# MCU.net
KiCad netlist of a schematic drawn in Altium Designer
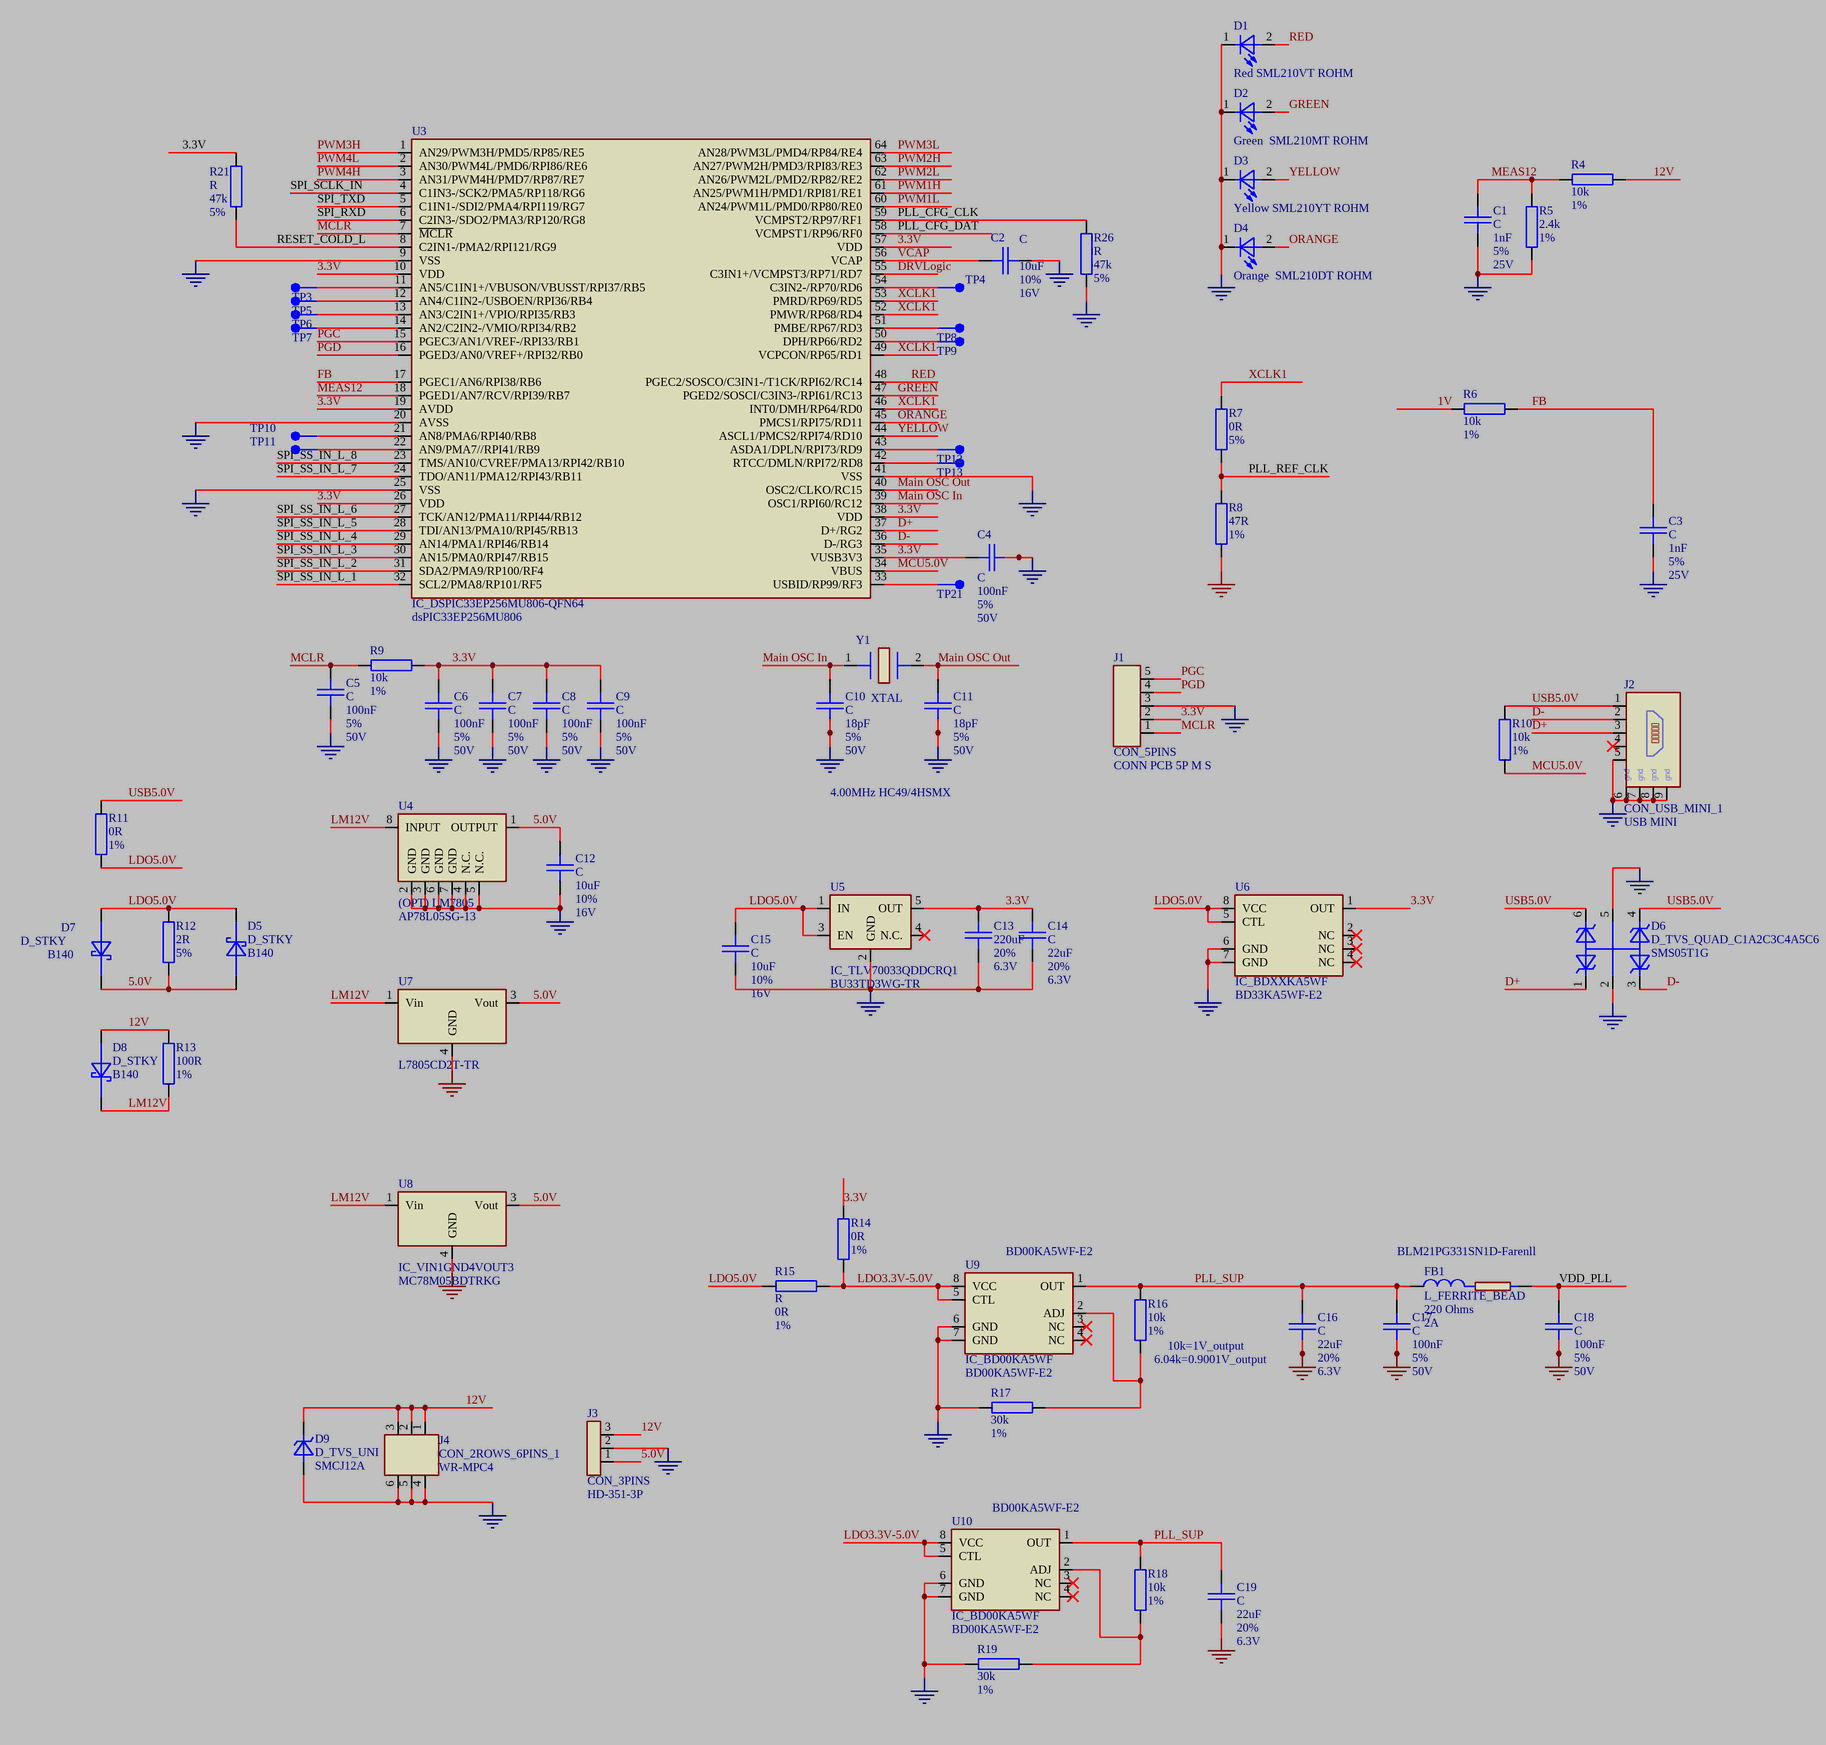
[diagram p0: MCU.SchDoc]

(export (version "E")
  (design (tool "Eeschema 10.0.6"))
  (components
    (comp (ref "C1")
      (value "C")
      (footprint "SMD_0603_CAPC1608X95N")
      (fields
        (field (name "DB_PART_NUMBER") "CAP000024113")
        (field (name "DB_VALUE") "1nF")
        (field (name "DB_TOLERANCE") "5%")
        (field (name "DB_VOLTAGE") "25V")
        (field (name "DB_MANUFACTURER_PART") "KEMET    C0603C102J3RAC")
        (field (name "DB_APPROVED_BY") "ISHIDDEN=T")
      )
      (libsource (lib "Database_Libs1") (part "C"))
    )
    (comp (ref "C2")
      (value "C")
      (footprint "SMD_0805_CAPC2012X145N")
      (fields
        (field (name "DB_PART_NUMBER") "CAP000043636")
        (field (name "DB_VALUE") "10uF")
        (field (name "DB_TOLERANCE") "10%")
        (field (name "DB_VOLTAGE") "16V")
        (field (name "DB_MANUFACTURER_PART") "KEMET    C0805C106K4PAC")
        (field (name "DB_APPROVED_BY") "ISHIDDEN=T")
      )
      (libsource (lib "Database_Libs1") (part "C"))
    )
    (comp (ref "C3")
      (value "C")
      (footprint "SMD_0603_CAPC1608X95N")
      (fields
        (field (name "DB_PART_NUMBER") "CAP000024113")
        (field (name "DB_VALUE") "1nF")
        (field (name "DB_TOLERANCE") "5%")
        (field (name "DB_VOLTAGE") "25V")
        (field (name "DB_MANUFACTURER_PART") "KEMET    C0603C102J3RAC")
        (field (name "DB_APPROVED_BY") "ISHIDDEN=T")
      )
      (libsource (lib "Database_Libs1") (part "C"))
    )
    (comp (ref "C4")
      (value "C")
      (footprint "SMD_0603_CAPC1608X95N")
      (fields
        (field (name "DB_PART_NUMBER") "CAP000027136")
        (field (name "DB_VALUE") "100nF")
        (field (name "DB_TOLERANCE") "5%")
        (field (name "DB_VOLTAGE") "50V")
        (field (name "DB_MANUFACTURER_PART") "KEMET    C0603C104J5RAC")
        (field (name "DB_APPROVED_BY") "ISHIDDEN=T")
      )
      (libsource (lib "Database_Libs1") (part "C"))
    )
    (comp (ref "C5")
      (value "C")
      (footprint "SMD_0603_CAPC1608X95N")
      (fields
        (field (name "DB_PART_NUMBER") "CAP000027136")
        (field (name "DB_VALUE") "100nF")
        (field (name "DB_TOLERANCE") "5%")
        (field (name "DB_VOLTAGE") "50V")
        (field (name "DB_MANUFACTURER_PART") "KEMET    C0603C104J5RAC")
        (field (name "DB_APPROVED_BY") "ISHIDDEN=T")
      )
      (libsource (lib "Database_Libs1") (part "C"))
    )
    (comp (ref "C6")
      (value "C")
      (footprint "SMD_0603_CAPC1608X95N")
      (fields
        (field (name "DB_PART_NUMBER") "CAP000027136")
        (field (name "DB_VALUE") "100nF")
        (field (name "DB_TOLERANCE") "5%")
        (field (name "DB_VOLTAGE") "50V")
        (field (name "DB_MANUFACTURER_PART") "KEMET    C0603C104J5RAC")
        (field (name "DB_APPROVED_BY") "ISHIDDEN=T")
      )
      (libsource (lib "Database_Libs1") (part "C"))
    )
    (comp (ref "C7")
      (value "C")
      (footprint "SMD_0603_CAPC1608X95N")
      (fields
        (field (name "DB_PART_NUMBER") "CAP000027136")
        (field (name "DB_VALUE") "100nF")
        (field (name "DB_TOLERANCE") "5%")
        (field (name "DB_VOLTAGE") "50V")
        (field (name "DB_MANUFACTURER_PART") "KEMET    C0603C104J5RAC")
        (field (name "DB_APPROVED_BY") "ISHIDDEN=T")
      )
      (libsource (lib "Database_Libs1") (part "C"))
    )
    (comp (ref "C8")
      (value "C")
      (footprint "SMD_0603_CAPC1608X95N")
      (fields
        (field (name "DB_PART_NUMBER") "CAP000027136")
        (field (name "DB_VALUE") "100nF")
        (field (name "DB_TOLERANCE") "5%")
        (field (name "DB_VOLTAGE") "50V")
        (field (name "DB_MANUFACTURER_PART") "KEMET    C0603C104J5RAC")
        (field (name "DB_APPROVED_BY") "ISHIDDEN=T")
      )
      (libsource (lib "Database_Libs1") (part "C"))
    )
    (comp (ref "C9")
      (value "C")
      (footprint "SMD_0603_CAPC1608X95N")
      (fields
        (field (name "DB_PART_NUMBER") "CAP000027136")
        (field (name "DB_VALUE") "100nF")
        (field (name "DB_TOLERANCE") "5%")
        (field (name "DB_VOLTAGE") "50V")
        (field (name "DB_MANUFACTURER_PART") "KEMET    C0603C104J5RAC")
        (field (name "DB_APPROVED_BY") "ISHIDDEN=T")
      )
      (libsource (lib "Database_Libs1") (part "C"))
    )
    (comp (ref "C10")
      (value "C")
      (footprint "SMD_0603_CAPC1608X95N")
      (fields
        (field (name "DB_PART_NUMBER") "CAP000031922")
        (field (name "DB_VALUE") "18pF")
        (field (name "DB_TOLERANCE") "5%")
        (field (name "DB_VOLTAGE") "50V")
        (field (name "DB_MANUFACTURER_PART") "KEMET    C0603C180J5GAC")
        (field (name "DB_APPROVED_BY") "ISHIDDEN=T")
      )
      (libsource (lib "Database_Libs1") (part "C"))
    )
    (comp (ref "C11")
      (value "C")
      (footprint "SMD_0603_CAPC1608X95N")
      (fields
        (field (name "DB_PART_NUMBER") "CAP000031922")
        (field (name "DB_VALUE") "18pF")
        (field (name "DB_TOLERANCE") "5%")
        (field (name "DB_VOLTAGE") "50V")
        (field (name "DB_MANUFACTURER_PART") "KEMET    C0603C180J5GAC")
        (field (name "DB_APPROVED_BY") "ISHIDDEN=T")
      )
      (libsource (lib "Database_Libs1") (part "C"))
    )
    (comp (ref "C12")
      (value "C")
      (footprint "SMD_0805_CAPC2012X145N")
      (fields
        (field (name "DB_PART_NUMBER") "CAP000043636")
        (field (name "DB_VALUE") "10uF")
        (field (name "DB_TOLERANCE") "10%")
        (field (name "DB_VOLTAGE") "16V")
        (field (name "DB_MANUFACTURER_PART") "KEMET    C0805C106K4PAC")
        (field (name "DB_APPROVED_BY") "ISHIDDEN=T")
      )
      (libsource (lib "Database_Libs1") (part "C"))
    )
    (comp (ref "C13")
      (value "C")
      (footprint "SMD_1210_CAPC3225X279N")
      (fields
        (field (name "DB_PART_NUMBER") "CAP000047355")
        (field (name "DB_VALUE") "220uF")
        (field (name "DB_TOLERANCE") "20%")
        (field (name "DB_VOLTAGE") "6.3V")
        (field (name "DB_MANUFACTURER_PART") "SAMSUNG    CL32A227MQVNNNE")
        (field (name "DB_APPROVED_BY") "VSN")
      )
      (libsource (lib "Database_Libs1") (part "C"))
    )
    (comp (ref "C14")
      (value "C")
      (footprint "SMD_0805_CAPC2012X145N")
      (fields
        (field (name "DB_PART_NUMBER") "CAP000043686")
        (field (name "DB_VALUE") "22uF")
        (field (name "DB_TOLERANCE") "20%")
        (field (name "DB_VOLTAGE") "6.3V")
        (field (name "DB_MANUFACTURER_PART") "KEMET    C0805C226M9PAC")
        (field (name "DB_APPROVED_BY") "ISHIDDEN=T")
      )
      (libsource (lib "Database_Libs1") (part "C"))
    )
    (comp (ref "C15")
      (value "C")
      (footprint "SMD_0805_CAPC2012X145N")
      (fields
        (field (name "DB_PART_NUMBER") "CAP000043636")
        (field (name "DB_VALUE") "10uF")
        (field (name "DB_TOLERANCE") "10%")
        (field (name "DB_VOLTAGE") "16V")
        (field (name "DB_MANUFACTURER_PART") "KEMET    C0805C106K4PAC")
        (field (name "DB_APPROVED_BY") "ISHIDDEN=T")
      )
      (libsource (lib "Database_Libs1") (part "C"))
    )
    (comp (ref "C16")
      (value "C")
      (footprint "SMD_0805_CAPC2012X145N")
      (fields
        (field (name "DB_PART_NUMBER") "CAP000043686")
        (field (name "DB_VALUE") "22uF")
        (field (name "DB_TOLERANCE") "20%")
        (field (name "DB_VOLTAGE") "6.3V")
        (field (name "DB_MANUFACTURER_PART") "KEMET    C0805C226M9PAC")
        (field (name "DB_APPROVED_BY") "ISHIDDEN=T")
      )
      (libsource (lib "Database_Libs1") (part "C"))
    )
    (comp (ref "C17")
      (value "C")
      (footprint "SMD_0603_CAPC1608X95N")
      (fields
        (field (name "DB_PART_NUMBER") "CAP000027136")
        (field (name "DB_VALUE") "100nF")
        (field (name "DB_TOLERANCE") "5%")
        (field (name "DB_VOLTAGE") "50V")
        (field (name "DB_MANUFACTURER_PART") "KEMET    C0603C104J5RAC")
        (field (name "DB_APPROVED_BY") "ISHIDDEN=T")
      )
      (libsource (lib "Database_Libs1") (part "C"))
    )
    (comp (ref "C18")
      (value "C")
      (footprint "SMD_0603_CAPC1608X95N")
      (fields
        (field (name "DB_PART_NUMBER") "CAP000027136")
        (field (name "DB_VALUE") "100nF")
        (field (name "DB_TOLERANCE") "5%")
        (field (name "DB_VOLTAGE") "50V")
        (field (name "DB_MANUFACTURER_PART") "KEMET    C0603C104J5RAC")
        (field (name "DB_APPROVED_BY") "ISHIDDEN=T")
      )
      (libsource (lib "Database_Libs1") (part "C"))
    )
    (comp (ref "C19")
      (value "C")
      (footprint "SMD_0805_CAPC2012X145N")
      (fields
        (field (name "DB_PART_NUMBER") "CAP000043686")
        (field (name "DB_VALUE") "22uF")
        (field (name "DB_TOLERANCE") "20%")
        (field (name "DB_VOLTAGE") "6.3V")
        (field (name "DB_MANUFACTURER_PART") "KEMET    C0805C226M9PAC")
        (field (name "DB_APPROVED_BY") "ISHIDDEN=T")
      )
      (libsource (lib "Database_Libs1") (part "C"))
    )
    (comp (ref "D1")
      (value "Red SML210VT ROHM")
      (footprint "SMD_0805_LED2012X100N")
      (libsource (lib "EPIQ_DND_CIS_Library") (part "LED_2"))
    )
    (comp (ref "D2")
      (value "Green 	SML210MT ROHM")
      (footprint "SMD_0805_LED2012X100N")
      (libsource (lib "EPIQ_DND_CIS_Library") (part "LED_2"))
    )
    (comp (ref "D3")
      (value "Yellow SML210YT ROHM")
      (footprint "SMD_0805_LED2012X100N")
      (libsource (lib "EPIQ_DND_CIS_Library") (part "LED_2"))
    )
    (comp (ref "D4")
      (value "Orange 	SML210DT ROHM")
      (footprint "SMD_0805_LED2012X100N")
      (libsource (lib "EPIQ_DND_CIS_Library") (part "LED_2"))
    )
    (comp (ref "D5")
      (value "D_STKY")
      (footprint "SMD_DO214AC_SMA")
      (fields
        (field (name "DB_PART_NUMBER") "DDE000000580")
        (field (name "DB_VALUE") "B140")
        (field (name "DB_MANUFACTURER_PART") "Diodes        B140")
        (field (name "DB_APPROVED_BY") "ISHIDDEN=T")
      )
      (libsource (lib "Database_Libs1") (part "D_STKY"))
    )
    (comp (ref "D6")
      (value "D_TVS_QUAD_C1A2C3C4A5C6")
      (footprint "SMD_SOT457_SOT95P275X110-6N")
      (fields
        (field (name "DB_PART_NUMBER") "DDE000002846")
        (field (name "DB_VALUE") "SMS05T1G")
        (field (name "DB_MANUFACTURER_PART") "ON SEMICONDUCTOR        SMS05T1G")
        (field (name "DB_APPROVED_BY") "VSN")
      )
      (libsource (lib "Database_Libs1") (part "D_TVS_QUAD_C1A2C3C4A5C6"))
    )
    (comp (ref "D7")
      (value "D_STKY")
      (footprint "SMD_DO214AC_SMA")
      (fields
        (field (name "DB_PART_NUMBER") "DDE000000580")
        (field (name "DB_VALUE") "B140")
        (field (name "DB_MANUFACTURER_PART") "Diodes        B140")
        (field (name "DB_APPROVED_BY") "ISHIDDEN=T")
      )
      (libsource (lib "Database_Libs1") (part "D_STKY"))
    )
    (comp (ref "D8")
      (value "D_STKY")
      (footprint "SMD_DO214AC_SMA")
      (fields
        (field (name "DB_PART_NUMBER") "DDE000000580")
        (field (name "DB_VALUE") "B140")
        (field (name "DB_MANUFACTURER_PART") "Diodes        B140")
        (field (name "DB_APPROVED_BY") "ISHIDDEN=T")
      )
      (libsource (lib "Database_Libs1") (part "D_STKY"))
    )
    (comp (ref "D9")
      (value "D_TVS_UNI")
      (footprint "SMD_DO214AC_SMC")
      (fields
        (field (name "DB_PART_NUMBER") "DDE000001725")
        (field (name "DB_VALUE") "SMCJ12A")
        (field (name "DB_MANUFACTURER_PART") "Diodes        SMCJ12A")
        (field (name "DB_APPROVED_BY") "ISHIDDEN=T")
      )
      (libsource (lib "Database_Libs1") (part "D_TVS_UNI"))
    )
    (comp (ref "FB1")
      (value "L_FERRITE_BEAD")
      (footprint "SMD_0805_INDC2012X105N")
      (fields
        (field (name "DB_PART_NUMBER") "IND000000029")
        (field (name "DB_VALUE") "220 Ohms")
        (field (name "DB_CURRENT") "2A")
        (field (name "DB_MANUFACTURER_PART") "MURATA       BLM21PG221SN1D")
        (field (name "DB_APPROVED_BY") "VSN")
      )
      (libsource (lib "Database_Libs1") (part "L_FERRITE_BEAD"))
    )
    (comp (ref "J1")
      (value "CON_5PINS")
      (footprint "PTH_HDRV05W64P254_1X05")
      (fields
        (field (name "DB_PART_NUMBER") "CON000000006")
        (field (name "DB_VALUE") "CONN PCB 5P M S")
        (field (name "DB_MANUFACTURER_PART") "W+P        143-12-005-00")
        (field (name "DB_APPROVED_BY") "VSN")
      )
      (libsource (lib "Database_Libs1") (part "CON_5PINS"))
    )
    (comp (ref "J2")
      (value "CON_USB_MINI_1")
      (footprint "SMD_CON-CVILUX-CU04-SCM15B0")
      (fields
        (field (name "DB_PART_NUMBER") "CON000000048")
        (field (name "DB_VALUE") "USB MINI")
        (field (name "DB_MANUFACTURER_PART") "CVILUX       CU04-SCM15B0-R0-LF")
        (field (name "DB_APPROVED_BY") "VSN")
      )
      (libsource (lib "Database_Libs1") (part "CON_USB_MINI_1"))
    )
    (comp (ref "J3")
      (value "CON_3PINS")
      (footprint "PTH_CON_HD-351-3P")
      (fields
        (field (name "DB_PART_NUMBER") "CON000000272")
        (field (name "DB_VALUE") "HD-351-3P")
        (field (name "DB_MANUFACTURER_PART") "HOW DER      HD-351-3P")
        (field (name "DB_APPROVED_BY") "VSN")
      )
      (libsource (lib "Database_Libs1") (part "CON_3PINS"))
    )
    (comp (ref "J4")
      (value "CON_2ROWS_6PINS_1")
      (footprint "PTH_CON_WR-MRC4-6P")
      (fields
        (field (name "DB_PART_NUMBER") "CON000000271")
        (field (name "DB_VALUE") "WR-MPC4")
        (field (name "DB_MANUFACTURER_PART") "WE         649 006 295 22")
        (field (name "DB_APPROVED_BY") "VSN")
      )
      (libsource (lib "Database_Libs1") (part "CON_2ROWS_6PINS_1"))
    )
    (comp (ref "R4")
      (value "R")
      (footprint "SMD_0603_RESC1608X55N")
      (fields
        (field (name "DB_PART_NUMBER") "RES000008663")
        (field (name "DB_VALUE") "10k")
        (field (name "DB_TOLERANCE") "1%")
        (field (name "DB_MANUFACTURER_PART") "YAGEO    RC0603FR-0710KL")
        (field (name "DB_APPROVED_BY") "VSN")
      )
      (libsource (lib "Database_Libs1") (part "R"))
    )
    (comp (ref "R5")
      (value "R")
      (footprint "SMD_0603_RESC1608X55N")
      (fields
        (field (name "DB_PART_NUMBER") "RES000006261")
        (field (name "DB_VALUE") "2.4k")
        (field (name "DB_TOLERANCE") "1%")
        (field (name "DB_MANUFACTURER_PART") "YAGEO    RC0603FR-072K4")
        (field (name "DB_APPROVED_BY") "ISHIDDEN=T")
      )
      (libsource (lib "Database_Libs1") (part "R"))
    )
    (comp (ref "R6")
      (value "R")
      (footprint "SMD_0603_RESC1608X55N")
      (fields
        (field (name "DB_PART_NUMBER") "RES000008663")
        (field (name "DB_VALUE") "10k")
        (field (name "DB_TOLERANCE") "1%")
        (field (name "DB_MANUFACTURER_PART") "YAGEO    RC0603FR-0710KL")
        (field (name "DB_APPROVED_BY") "VSN")
      )
      (libsource (lib "Database_Libs1") (part "R"))
    )
    (comp (ref "R7")
      (value "R")
      (footprint "SMD_0603_RESC1608X55N")
      (fields
        (field (name "DB_PART_NUMBER") "RES000006349")
        (field (name "DB_VALUE") "0R")
        (field (name "DB_TOLERANCE") "5%")
        (field (name "DB_MANUFACTURER_PART") "YAGEO    RC0603JR-070R")
      )
      (libsource (lib "Database_Libs1") (part "R"))
    )
    (comp (ref "R8")
      (value "R")
      (footprint "SMD_0603_RESC1608X55N")
      (fields
        (field (name "DB_PART_NUMBER") "RES000006220")
        (field (name "DB_VALUE") "47R")
        (field (name "DB_TOLERANCE") "1%")
        (field (name "DB_MANUFACTURER_PART") "YAGEO    RC0603FR-0747R")
        (field (name "DB_APPROVED_BY") "ISHIDDEN=T")
      )
      (libsource (lib "Database_Libs1") (part "R"))
    )
    (comp (ref "R9")
      (value "R")
      (footprint "SMD_0603_RESC1608X55N")
      (fields
        (field (name "DB_PART_NUMBER") "RES000008663")
        (field (name "DB_VALUE") "10k")
        (field (name "DB_TOLERANCE") "1%")
        (field (name "DB_MANUFACTURER_PART") "YAGEO    RC0603FR-0710KL")
        (field (name "DB_APPROVED_BY") "VSN")
      )
      (libsource (lib "Database_Libs1") (part "R"))
    )
    (comp (ref "R10")
      (value "R")
      (footprint "SMD_0603_RESC1608X55N")
      (fields
        (field (name "DB_PART_NUMBER") "RES000008663")
        (field (name "DB_VALUE") "10k")
        (field (name "DB_TOLERANCE") "1%")
        (field (name "DB_MANUFACTURER_PART") "YAGEO    RC0603FR-0710KL")
        (field (name "DB_APPROVED_BY") "VSN")
      )
      (libsource (lib "Database_Libs1") (part "R"))
    )
    (comp (ref "R11")
      (value "R")
      (footprint "SMD_0603_RESC1608X55N")
      (fields
        (field (name "DB_PART_NUMBER") "RES000008926")
        (field (name "DB_VALUE") "0R")
        (field (name "DB_TOLERANCE") "1%")
        (field (name "DB_MANUFACTURER_PART") "YAGEO    AC0603FR-070RL")
        (field (name "DB_APPROVED_BY") "VSN")
      )
      (libsource (lib "Database_Libs1") (part "R"))
    )
    (comp (ref "R12")
      (value "R")
      (footprint "SMD_1206_RESC3216X65N")
      (fields
        (field (name "DB_PART_NUMBER") "RES000007051")
        (field (name "DB_VALUE") "2R")
        (field (name "DB_TOLERANCE") "5%")
        (field (name "DB_MANUFACTURER_PART") "YAGEO    RC1206JR-072R")
        (field (name "DB_APPROVED_BY") "ISHIDDEN=T")
      )
      (libsource (lib "Database_Libs1") (part "R"))
    )
    (comp (ref "R13")
      (value "R")
      (footprint "SMD_1206_RESC3216X65N")
      (fields
        (field (name "DB_PART_NUMBER") "RES000006922")
        (field (name "DB_VALUE") "100R")
        (field (name "DB_TOLERANCE") "1%")
        (field (name "DB_MANUFACTURER_PART") "YAGEO    RC1206FR-07100R")
        (field (name "DB_APPROVED_BY") "ISHIDDEN=T")
      )
      (libsource (lib "Database_Libs1") (part "R"))
    )
    (comp (ref "R14")
      (value "R")
      (footprint "SMD_1206_RESC3216X65N")
      (fields
        (field (name "DB_PART_NUMBER") "RES000008756")
        (field (name "DB_VALUE") "0R")
        (field (name "DB_TOLERANCE") "1%")
        (field (name "DB_MANUFACTURER_PART") "YAGEO    AC1206FR-070RL")
        (field (name "DB_APPROVED_BY") "VSN")
      )
      (libsource (lib "Database_Libs1") (part "R"))
    )
    (comp (ref "R15")
      (value "R")
      (footprint "SMD_1206_RESC3216X65N")
      (fields
        (field (name "DB_PART_NUMBER") "RES000008756")
        (field (name "DB_VALUE") "0R")
        (field (name "DB_TOLERANCE") "1%")
        (field (name "DB_MANUFACTURER_PART") "YAGEO    AC1206FR-070RL")
        (field (name "DB_APPROVED_BY") "VSN")
      )
      (libsource (lib "Database_Libs1") (part "R"))
    )
    (comp (ref "R16")
      (value "R")
      (footprint "SMD_0603_RESC1608X55N")
      (fields
        (field (name "DB_PART_NUMBER") "RES000008663")
        (field (name "DB_VALUE") "10k")
        (field (name "DB_TOLERANCE") "1%")
        (field (name "DB_MANUFACTURER_PART") "YAGEO    RC0603FR-0710KL")
        (field (name "DB_APPROVED_BY") "VSN")
      )
      (libsource (lib "Database_Libs1") (part "R"))
    )
    (comp (ref "R17")
      (value "R")
      (footprint "SMD_0603_RESC1608X55N")
      (fields
        (field (name "DB_PART_NUMBER") "RES000006287")
        (field (name "DB_VALUE") "30k")
        (field (name "DB_TOLERANCE") "1%")
        (field (name "DB_MANUFACTURER_PART") "YAGEO    RC0603FR-0730K")
        (field (name "DB_APPROVED_BY") "ISHIDDEN=T")
      )
      (libsource (lib "Database_Libs1") (part "R"))
    )
    (comp (ref "R18")
      (value "R")
      (footprint "SMD_0603_RESC1608X55N")
      (fields
        (field (name "DB_PART_NUMBER") "RES000008663")
        (field (name "DB_VALUE") "10k")
        (field (name "DB_TOLERANCE") "1%")
        (field (name "DB_MANUFACTURER_PART") "YAGEO    RC0603FR-0710KL")
        (field (name "DB_APPROVED_BY") "VSN")
      )
      (libsource (lib "Database_Libs1") (part "R"))
    )
    (comp (ref "R19")
      (value "R")
      (footprint "SMD_0603_RESC1608X55N")
      (fields
        (field (name "DB_PART_NUMBER") "RES000006287")
        (field (name "DB_VALUE") "30k")
        (field (name "DB_TOLERANCE") "1%")
        (field (name "DB_MANUFACTURER_PART") "YAGEO    RC0603FR-0730K")
        (field (name "DB_APPROVED_BY") "ISHIDDEN=T")
      )
      (libsource (lib "Database_Libs1") (part "R"))
    )
    (comp (ref "R21")
      (value "R")
      (footprint "SMD_0603_RESC1608X55N")
      (fields
        (field (name "DB_PART_NUMBER") "RES000006462")
        (field (name "DB_VALUE") "47k")
        (field (name "DB_TOLERANCE") "5%")
        (field (name "DB_MANUFACTURER_PART") "YAGEO    RC0603JR-0747K")
      )
      (libsource (lib "Database_Libs1") (part "R"))
    )
    (comp (ref "R26")
      (value "R")
      (footprint "SMD_0603_RESC1608X55N")
      (fields
        (field (name "DB_PART_NUMBER") "RES000006462")
        (field (name "DB_VALUE") "47k")
        (field (name "DB_TOLERANCE") "5%")
        (field (name "DB_MANUFACTURER_PART") "YAGEO    RC0603JR-0747K")
      )
      (libsource (lib "Database_Libs1") (part "R"))
    )
    (comp (ref "TP3")
      (value "TEST_POINT_1")
      (footprint "SMD_TP_100-254")
      (fields
        (field (name "DB_PART_NUMBER") "TPO000000001")
        (field (name "DB_MANUFACTURER_PART") "ISHIDDEN=T")
        (field (name "DB_APPROVED_BY") "ISHIDDEN=T")
      )
      (libsource (lib "Database_Libs1") (part "TEST_POINT_1"))
    )
    (comp (ref "TP4")
      (value "TEST_POINT_1")
      (footprint "SMD_TP_100-254")
      (fields
        (field (name "DB_PART_NUMBER") "TPO000000001")
        (field (name "DB_MANUFACTURER_PART") "ISHIDDEN=T")
        (field (name "DB_APPROVED_BY") "ISHIDDEN=T")
      )
      (libsource (lib "Database_Libs1") (part "TEST_POINT_1"))
    )
    (comp (ref "TP5")
      (value "TEST_POINT_1")
      (footprint "SMD_TP_100-254")
      (fields
        (field (name "DB_PART_NUMBER") "TPO000000001")
        (field (name "DB_MANUFACTURER_PART") "ISHIDDEN=T")
        (field (name "DB_APPROVED_BY") "ISHIDDEN=T")
      )
      (libsource (lib "Database_Libs1") (part "TEST_POINT_1"))
    )
    (comp (ref "TP6")
      (value "TEST_POINT_1")
      (footprint "SMD_TP_100-254")
      (fields
        (field (name "DB_PART_NUMBER") "TPO000000001")
        (field (name "DB_MANUFACTURER_PART") "ISHIDDEN=T")
        (field (name "DB_APPROVED_BY") "ISHIDDEN=T")
      )
      (libsource (lib "Database_Libs1") (part "TEST_POINT_1"))
    )
    (comp (ref "TP7")
      (value "TEST_POINT_1")
      (footprint "SMD_TP_100-254")
      (fields
        (field (name "DB_PART_NUMBER") "TPO000000001")
        (field (name "DB_MANUFACTURER_PART") "ISHIDDEN=T")
        (field (name "DB_APPROVED_BY") "ISHIDDEN=T")
      )
      (libsource (lib "Database_Libs1") (part "TEST_POINT_1"))
    )
    (comp (ref "TP8")
      (value "TEST_POINT_1")
      (footprint "SMD_TP_100-254")
      (fields
        (field (name "DB_PART_NUMBER") "TPO000000001")
        (field (name "DB_MANUFACTURER_PART") "ISHIDDEN=T")
        (field (name "DB_APPROVED_BY") "ISHIDDEN=T")
      )
      (libsource (lib "Database_Libs1") (part "TEST_POINT_1"))
    )
    (comp (ref "TP9")
      (value "TEST_POINT_1")
      (footprint "SMD_TP_100-254")
      (fields
        (field (name "DB_PART_NUMBER") "TPO000000001")
        (field (name "DB_MANUFACTURER_PART") "ISHIDDEN=T")
        (field (name "DB_APPROVED_BY") "ISHIDDEN=T")
      )
      (libsource (lib "Database_Libs1") (part "TEST_POINT_1"))
    )
    (comp (ref "TP10")
      (value "TEST_POINT_1")
      (footprint "SMD_TP_100-254")
      (fields
        (field (name "DB_PART_NUMBER") "TPO000000001")
        (field (name "DB_MANUFACTURER_PART") "ISHIDDEN=T")
        (field (name "DB_APPROVED_BY") "ISHIDDEN=T")
      )
      (libsource (lib "Database_Libs1") (part "TEST_POINT_1"))
    )
    (comp (ref "TP11")
      (value "TEST_POINT_1")
      (footprint "SMD_TP_100-254")
      (fields
        (field (name "DB_PART_NUMBER") "TPO000000001")
        (field (name "DB_MANUFACTURER_PART") "ISHIDDEN=T")
        (field (name "DB_APPROVED_BY") "ISHIDDEN=T")
      )
      (libsource (lib "Database_Libs1") (part "TEST_POINT_1"))
    )
    (comp (ref "TP12")
      (value "TEST_POINT_1")
      (footprint "SMD_TP_100-254")
      (fields
        (field (name "DB_PART_NUMBER") "TPO000000001")
        (field (name "DB_MANUFACTURER_PART") "ISHIDDEN=T")
        (field (name "DB_APPROVED_BY") "ISHIDDEN=T")
      )
      (libsource (lib "Database_Libs1") (part "TEST_POINT_1"))
    )
    (comp (ref "TP13")
      (value "TEST_POINT_1")
      (footprint "SMD_TP_100-254")
      (fields
        (field (name "DB_PART_NUMBER") "TPO000000001")
        (field (name "DB_MANUFACTURER_PART") "ISHIDDEN=T")
        (field (name "DB_APPROVED_BY") "ISHIDDEN=T")
      )
      (libsource (lib "Database_Libs1") (part "TEST_POINT_1"))
    )
    (comp (ref "TP21")
      (value "TEST_POINT_1")
      (footprint "SMD_TP_100-254")
      (fields
        (field (name "DB_PART_NUMBER") "TPO000000001")
        (field (name "DB_MANUFACTURER_PART") "ISHIDDEN=T")
        (field (name "DB_APPROVED_BY") "ISHIDDEN=T")
      )
      (libsource (lib "Database_Libs1") (part "TEST_POINT_1"))
    )
    (comp (ref "U3")
      (value "IC_DSPIC33EP256MU806-QFN64")
      (footprint "SMD_QFP50P1200X1200X120-64N")
      (fields
        (field (name "DB_PART_NUMBER") "MCU000000070")
        (field (name "DB_VALUE") "dsPIC33EP256MU806")
        (field (name "DB_MANUFACTURER_PART") "MICROCHIP        DSPIC33EP256MU806-E/PT")
        (field (name "DB_APPROVED_BY") "VSN")
      )
      (libsource (lib "Database_Libs1") (part "IC_DSPIC33EP256MU806-QFN64"))
    )
    (comp (ref "U4")
      (value "(OPT) LM7805")
      (footprint "SMD_SOIC127P600X175-8N")
      (fields
        (field (name "DB_PART_NUMBER") "PSU000000125")
        (field (name "DB_VALUE") "AP78L05SG-13")
        (field (name "DB_MANUFACTURER_PART") "DIODES        AP78L05SG-13")
        (field (name "DB_APPROVED_BY") "VSN")
      )
      (libsource (lib "Database_Libs1") (part "IC_LM2931AD-5.0R2G_SO-8"))
    )
    (comp (ref "U5")
      (value "IC_TLV70033QDDCRQ1")
      (footprint "SMD_SOT95P280X135-5N")
      (fields
        (field (name "DB_PART_NUMBER") "PSU000000126")
        (field (name "DB_VALUE") "BU33TD3WG-TR")
        (field (name "DB_MANUFACTURER_PART") "ROHM     BU33TD3WG-TR")
        (field (name "DB_APPROVED_BY") "VSN")
      )
      (libsource (lib "Database_Libs1") (part "IC_TLV70033QDDCRQ1"))
    )
    (comp (ref "U6")
      (value "IC_BDXXKA5WF")
      (footprint "SMD_SOIC127P620X160-8N")
      (fields
        (field (name "DB_PART_NUMBER") "PSU000000127")
        (field (name "DB_VALUE") "BD33KA5WF-E2")
        (field (name "DB_MANUFACTURER_PART") "ROHM        BD33KA5WF-E2")
        (field (name "DB_APPROVED_BY") "VSN")
      )
      (libsource (lib "Database_Libs1") (part "IC_BDXXKA5WF"))
    )
    (comp (ref "U7")
      (value "IC_IN1OUT3GND4")
      (footprint "SMD_TO254P1542X460-3_4N")
      (fields
        (field (name "DB_PART_NUMBER") "PSU000000129")
        (field (name "DB_VALUE") "L7805CD2T-TR")
        (field (name "DB_MANUFACTURER_PART") "ST       L7805CD2T-TR")
        (field (name "DB_APPROVED_BY") "VSN")
      )
      (libsource (lib "Database_Libs1") (part "IC_IN1OUT3GND4"))
    )
    (comp (ref "U8")
      (value "IC_VIN1GND4VOUT3")
      (footprint "SMD_TO229P991X239-4N_DPAK")
      (fields
        (field (name "DB_PART_NUMBER") "PSU000000031")
        (field (name "DB_VALUE") "MC78M05BDTRKG")
        (field (name "DB_MANUFACTURER_PART") "ON Semiconductor       MC78M05BDTRKG")
        (field (name "DB_APPROVED_BY") "VSN")
      )
      (libsource (lib "Database_Libs1") (part "IC_VIN1GND4VOUT3"))
    )
    (comp (ref "U9")
      (value "IC_BD00KA5WF")
      (footprint "SMD_SOIC127P620X160-8N")
      (fields
        (field (name "DB_PART_NUMBER") "PSU000000128")
        (field (name "DB_VALUE") "BD00KA5WF-E2")
        (field (name "DB_MANUFACTURER_PART") "ROHM        BD00KA5WF-E2")
        (field (name "DB_APPROVED_BY") "VSN")
      )
      (libsource (lib "Database_Libs1") (part "IC_BD00KA5WF"))
    )
    (comp (ref "U10")
      (value "IC_BD00KA5WF")
      (footprint "SMD_SOIC127P620X160-8N")
      (fields
        (field (name "DB_PART_NUMBER") "PSU000000128")
        (field (name "DB_VALUE") "BD00KA5WF-E2")
        (field (name "DB_MANUFACTURER_PART") "ROHM        BD00KA5WF-E2")
        (field (name "DB_APPROVED_BY") "VSN")
      )
      (libsource (lib "Database_Libs1") (part "IC_BD00KA5WF"))
    )
    (comp (ref "Y1")
      (value "XTAL")
      (footprint "SMD_HC49_XTAL1140X480X420N")
      (fields
        (field (name "DB_PART_NUMBER") "OSC000000012")
        (field (name "DB_VALUE") "4.00MHz HC49/4HSMX")
        (field (name "DB_MANUFACTURER_PART") "IQD       4.00MHz HC49/4HSMX")
        (field (name "DB_APPROVED_BY") "VSN")
      )
      (libsource (lib "Database_Libs1") (part "XTAL"))
    )
  )
  (nets
    (net (code "1") (name "/1V") (class "Default")
      (node (ref "R6") (pin "2") (pinfunction "2_2") (pintype "passive"))
    )
    (net (code "2") (name "/3.3V") (class "Default")
      (node (ref "C13") (pin "2") (pinfunction "2_2") (pintype "passive"))
      (node (ref "C14") (pin "1") (pinfunction "1_1") (pintype "passive"))
      (node (ref "C4") (pin "1") (pinfunction "1_1") (pintype "passive"))
      (node (ref "C6") (pin "1") (pinfunction "1_1") (pintype "passive"))
      (node (ref "C7") (pin "1") (pinfunction "1_1") (pintype "passive"))
      (node (ref "C8") (pin "1") (pinfunction "1_1") (pintype "passive"))
      (node (ref "C9") (pin "1") (pinfunction "1_1") (pintype "passive"))
      (node (ref "J1") (pin "2") (pinfunction "2_2") (pintype "passive"))
      (node (ref "R14") (pin "2") (pinfunction "2_2") (pintype "passive"))
      (node (ref "R21") (pin "1") (pinfunction "1_1") (pintype "passive"))
      (node (ref "R9") (pin "2") (pinfunction "2_2") (pintype "passive"))
      (node (ref "U3") (pin "10") (pinfunction "VDD_10") (pintype "passive"))
      (node (ref "U3") (pin "19") (pinfunction "AVDD_19") (pintype "passive"))
      (node (ref "U3") (pin "26") (pinfunction "VDD_26") (pintype "passive"))
      (node (ref "U3") (pin "35") (pinfunction "VUSB3V3_35") (pintype "passive"))
      (node (ref "U3") (pin "38") (pinfunction "VDD_38") (pintype "passive"))
      (node (ref "U3") (pin "57") (pinfunction "VDD_57") (pintype "passive"))
      (node (ref "U5") (pin "5") (pinfunction "OUT_5") (pintype "passive"))
      (node (ref "U6") (pin "1") (pinfunction "OUT_1") (pintype "passive"))
    )
    (net (code "3") (name "/5.0V") (class "Default")
      (node (ref "C12") (pin "1") (pinfunction "1_1") (pintype "passive"))
      (node (ref "D5") (pin "2") (pinfunction "A_2") (pintype "passive"))
      (node (ref "D7") (pin "1") (pinfunction "C_1") (pintype "passive"))
      (node (ref "J3") (pin "1") (pinfunction "1_1") (pintype "passive"))
      (node (ref "R12") (pin "1") (pinfunction "1_1") (pintype "passive"))
      (node (ref "U4") (pin "1") (pinfunction "OUTPUT_1") (pintype "passive"))
      (node (ref "U7") (pin "3") (pinfunction "Vout_3") (pintype "passive"))
      (node (ref "U8") (pin "3") (pinfunction "Vout_3") (pintype "passive"))
    )
    (net (code "4") (name "/12V") (class "Default")
      (node (ref "D8") (pin "2") (pinfunction "A_2") (pintype "passive"))
      (node (ref "D9") (pin "1") (pinfunction "C_1") (pintype "passive"))
      (node (ref "J3") (pin "3") (pinfunction "3_3") (pintype "passive"))
      (node (ref "J4") (pin "1") (pinfunction "1_1") (pintype "passive"))
      (node (ref "J4") (pin "2") (pinfunction "2_2") (pintype "passive"))
      (node (ref "J4") (pin "3") (pinfunction "3_3") (pintype "passive"))
      (node (ref "R13") (pin "2") (pinfunction "2_2") (pintype "passive"))
      (node (ref "R4") (pin "1") (pinfunction "1_1") (pintype "passive"))
    )
    (net (code "5") (name "/D+") (class "Default")
      (node (ref "D6") (pin "1") (pinfunction "1_1") (pintype "passive"))
      (node (ref "J2") (pin "3") (pinfunction "3_3") (pintype "passive"))
      (node (ref "U3") (pin "37") (pinfunction "D+/RG2_37") (pintype "passive"))
    )
    (net (code "6") (name "/D-") (class "Default")
      (node (ref "D6") (pin "3") (pinfunction "3_3") (pintype "passive"))
      (node (ref "J2") (pin "2") (pinfunction "2_2") (pintype "passive"))
      (node (ref "U3") (pin "36") (pinfunction "D-/RG3_36") (pintype "passive"))
    )
    (net (code "7") (name "/DRVLogic") (class "Default")
      (node (ref "U3") (pin "55") (pinfunction "C3IN1+/VCMPST3/RP71/RD7_55") (pintype "passive"))
    )
    (net (code "8") (name "/FB") (class "Default")
      (node (ref "C3") (pin "1") (pinfunction "1_1") (pintype "passive"))
      (node (ref "R6") (pin "1") (pinfunction "1_1") (pintype "passive"))
      (node (ref "U3") (pin "17") (pinfunction "PGEC1/AN6/RPI38/RB6_17") (pintype "passive"))
    )
    (net (code "9") (name "/GREEN") (class "Default")
      (node (ref "D2") (pin "2") (pinfunction "A_2") (pintype "passive"))
      (node (ref "U3") (pin "47") (pinfunction "PGED2/SOSCI/C3IN3-/RPI61/RC13_47") (pintype "passive"))
    )
    (net (code "10") (name "/LDO3.3V-5.0V") (class "Default")
      (node (ref "R14") (pin "1") (pinfunction "1_1") (pintype "passive"))
      (node (ref "R15") (pin "1") (pinfunction "1_1") (pintype "passive"))
      (node (ref "U10") (pin "5") (pinfunction "CTL_5") (pintype "passive"))
      (node (ref "U10") (pin "8") (pinfunction "VCC_8") (pintype "passive"))
      (node (ref "U9") (pin "5") (pinfunction "CTL_5") (pintype "passive"))
      (node (ref "U9") (pin "8") (pinfunction "VCC_8") (pintype "passive"))
    )
    (net (code "11") (name "/LDO5.0V") (class "Default")
      (node (ref "C15") (pin "1") (pinfunction "1_1") (pintype "passive"))
      (node (ref "D5") (pin "1") (pinfunction "C_1") (pintype "passive"))
      (node (ref "D7") (pin "2") (pinfunction "A_2") (pintype "passive"))
      (node (ref "R11") (pin "1") (pinfunction "1_1") (pintype "passive"))
      (node (ref "R12") (pin "2") (pinfunction "2_2") (pintype "passive"))
      (node (ref "R15") (pin "2") (pinfunction "2_2") (pintype "passive"))
      (node (ref "U5") (pin "1") (pinfunction "IN_1") (pintype "passive"))
      (node (ref "U5") (pin "3") (pinfunction "EN_3") (pintype "passive"))
      (node (ref "U6") (pin "5") (pinfunction "CTL_5") (pintype "passive"))
      (node (ref "U6") (pin "8") (pinfunction "VCC_8") (pintype "passive"))
    )
    (net (code "12") (name "/LM12V") (class "Default")
      (node (ref "D8") (pin "1") (pinfunction "C_1") (pintype "passive"))
      (node (ref "R13") (pin "1") (pinfunction "1_1") (pintype "passive"))
      (node (ref "U4") (pin "8") (pinfunction "INPUT_8") (pintype "passive"))
      (node (ref "U7") (pin "1") (pinfunction "Vin_1") (pintype "passive"))
      (node (ref "U8") (pin "1") (pinfunction "Vin_1") (pintype "passive"))
    )
    (net (code "13") (name "/MCLR") (class "Default")
      (node (ref "C5") (pin "1") (pinfunction "1_1") (pintype "passive"))
      (node (ref "J1") (pin "1") (pinfunction "1_1") (pintype "passive"))
      (node (ref "R9") (pin "1") (pinfunction "1_1") (pintype "passive"))
      (node (ref "U3") (pin "7") (pinfunction "~{MCLR}_7") (pintype "passive"))
    )
    (net (code "14") (name "/MCU5.0V") (class "Default")
      (node (ref "R10") (pin "2") (pinfunction "2_2") (pintype "passive"))
      (node (ref "U3") (pin "34") (pinfunction "VBUS_34") (pintype "passive"))
    )
    (net (code "15") (name "/MEAS12") (class "Default")
      (node (ref "C1") (pin "1") (pinfunction "1_1") (pintype "passive"))
      (node (ref "R4") (pin "2") (pinfunction "2_2") (pintype "passive"))
      (node (ref "R5") (pin "2") (pinfunction "2_2") (pintype "passive"))
      (node (ref "U3") (pin "18") (pinfunction "PGED1/AN7/RCV/RPI39/RB7_18") (pintype "passive"))
    )
    (net (code "16") (name "/Main OSC In") (class "Default")
      (node (ref "C10") (pin "1") (pinfunction "1_1") (pintype "passive"))
      (node (ref "U3") (pin "39") (pinfunction "OSC1/RPI60/RC12_39") (pintype "passive"))
      (node (ref "Y1") (pin "1") (pinfunction "1_1") (pintype "passive"))
    )
    (net (code "17") (name "/Main OSC Out") (class "Default")
      (node (ref "C11") (pin "1") (pinfunction "1_1") (pintype "passive"))
      (node (ref "U3") (pin "40") (pinfunction "OSC2/CLKO/RC15_40") (pintype "passive"))
      (node (ref "Y1") (pin "2") (pinfunction "2_2") (pintype "passive"))
    )
    (net (code "18") (name "/ORANGE") (class "Default")
      (node (ref "D4") (pin "2") (pinfunction "A_2") (pintype "passive"))
      (node (ref "U3") (pin "45") (pinfunction "PMCS1/RPI75/RD11_45") (pintype "passive"))
    )
    (net (code "19") (name "/PGC") (class "Default")
      (node (ref "J1") (pin "5") (pinfunction "5_5") (pintype "passive"))
      (node (ref "U3") (pin "15") (pinfunction "PGEC3/AN1/VREF-/RPI33/RB1_15") (pintype "passive"))
    )
    (net (code "20") (name "/PGD") (class "Default")
      (node (ref "J1") (pin "4") (pinfunction "4_4") (pintype "passive"))
      (node (ref "U3") (pin "16") (pinfunction "PGED3/AN0/VREF+/RPI32/RB0_16") (pintype "passive"))
    )
    (net (code "21") (name "/PLL_CFG_CLK") (class "Default")
      (node (ref "R26") (pin "1") (pinfunction "1_1") (pintype "passive"))
      (node (ref "U3") (pin "59") (pinfunction "VCMPST2/RP97/RF1_59") (pintype "passive"))
    )
    (net (code "22") (name "/PLL_CFG_DAT") (class "Default")
      (node (ref "U3") (pin "58") (pinfunction "VCMPST1/RP96/RF0_58") (pintype "passive"))
    )
    (net (code "23") (name "/PLL_REF_CLK") (class "Default")
      (node (ref "R7") (pin "1") (pinfunction "1_1") (pintype "passive"))
      (node (ref "R8") (pin "1") (pinfunction "1_1") (pintype "passive"))
    )
    (net (code "24") (name "/PLL_SUP") (class "Default")
      (node (ref "C16") (pin "1") (pinfunction "1_1") (pintype "passive"))
      (node (ref "C17") (pin "1") (pinfunction "1_1") (pintype "passive"))
      (node (ref "C19") (pin "1") (pinfunction "1_1") (pintype "passive"))
      (node (ref "FB1") (pin "1") (pinfunction "1_1") (pintype "passive"))
      (node (ref "R16") (pin "1") (pinfunction "1_1") (pintype "passive"))
      (node (ref "R18") (pin "1") (pinfunction "1_1") (pintype "passive"))
      (node (ref "U10") (pin "1") (pinfunction "OUT_1") (pintype "passive"))
      (node (ref "U9") (pin "1") (pinfunction "OUT_1") (pintype "passive"))
    )
    (net (code "25") (name "/PWM1H") (class "Default")
      (node (ref "U3") (pin "61") (pinfunction "AN25/PWM1H/PMD1/RPI81/RE1_61") (pintype "passive"))
    )
    (net (code "26") (name "/PWM1L") (class "Default")
      (node (ref "U3") (pin "60") (pinfunction "AN24/PWM1L/PMD0/RP80/RE0_60") (pintype "passive"))
    )
    (net (code "27") (name "/PWM2H") (class "Default")
      (node (ref "U3") (pin "63") (pinfunction "AN27/PWM2H/PMD3/RPI83/RE3_63") (pintype "passive"))
    )
    (net (code "28") (name "/PWM2L") (class "Default")
      (node (ref "U3") (pin "62") (pinfunction "AN26/PWM2L/PMD2/RP82/RE2_62") (pintype "passive"))
    )
    (net (code "29") (name "/PWM3H") (class "Default")
      (node (ref "U3") (pin "1") (pinfunction "AN29/PWM3H/PMD5/RP85/RE5_1") (pintype "passive"))
    )
    (net (code "30") (name "/PWM3L") (class "Default")
      (node (ref "U3") (pin "64") (pinfunction "AN28/PWM3L/PMD4/RP84/RE4_64") (pintype "passive"))
    )
    (net (code "31") (name "/PWM4H") (class "Default")
      (node (ref "U3") (pin "3") (pinfunction "AN31/PWM4H/PMD7/RP87/RE7_3") (pintype "passive"))
    )
    (net (code "32") (name "/PWM4L") (class "Default")
      (node (ref "U3") (pin "2") (pinfunction "AN30/PWM4L/PMD6/RPI86/RE6_2") (pintype "passive"))
    )
    (net (code "33") (name "/RED") (class "Default")
      (node (ref "D1") (pin "2") (pinfunction "A_2") (pintype "passive"))
      (node (ref "U3") (pin "48") (pinfunction "PGEC2/SOSCO/C3IN1-/T1CK/RPI62/RC14_48") (pintype "passive"))
    )
    (net (code "34") (name "/RESET_COLD_L") (class "Default")
      (node (ref "R21") (pin "2") (pinfunction "2_2") (pintype "passive"))
      (node (ref "U3") (pin "8") (pinfunction "C2IN1-/PMA2/RPI121/RG9_8") (pintype "passive"))
    )
    (net (code "35") (name "/SPI_RXD") (class "Default")
      (node (ref "U3") (pin "6") (pinfunction "C2IN3-/SDO2/PMA3/RP120/RG8_6") (pintype "passive"))
    )
    (net (code "36") (name "/SPI_SCLK_IN") (class "Default")
      (node (ref "U3") (pin "4") (pinfunction "C1IN3-/SCK2/PMA5/RP118/RG6_4") (pintype "passive"))
    )
    (net (code "37") (name "/SPI_SS_IN_L_1") (class "Default")
      (node (ref "U3") (pin "32") (pinfunction "SCL2/PMA8/RP101/RF5_32") (pintype "passive"))
    )
    (net (code "38") (name "/SPI_SS_IN_L_2") (class "Default")
      (node (ref "U3") (pin "31") (pinfunction "SDA2/PMA9/RP100/RF4_31") (pintype "passive"))
    )
    (net (code "39") (name "/SPI_SS_IN_L_3") (class "Default")
      (node (ref "U3") (pin "30") (pinfunction "AN15/PMA0/RPI47/RB15_30") (pintype "passive"))
    )
    (net (code "40") (name "/SPI_SS_IN_L_4") (class "Default")
      (node (ref "U3") (pin "29") (pinfunction "AN14/PMA1/RPI46/RB14_29") (pintype "passive"))
    )
    (net (code "41") (name "/SPI_SS_IN_L_5") (class "Default")
      (node (ref "U3") (pin "28") (pinfunction "TDI/AN13/PMA10/RPI45/RB13_28") (pintype "passive"))
    )
    (net (code "42") (name "/SPI_SS_IN_L_6") (class "Default")
      (node (ref "U3") (pin "27") (pinfunction "TCK/AN12/PMA11/RPI44/RB12_27") (pintype "passive"))
    )
    (net (code "43") (name "/SPI_SS_IN_L_7") (class "Default")
      (node (ref "U3") (pin "24") (pinfunction "TDO/AN11/PMA12/RPI43/RB11_24") (pintype "passive"))
    )
    (net (code "44") (name "/SPI_SS_IN_L_8") (class "Default")
      (node (ref "U3") (pin "23") (pinfunction "TMS/AN10/CVREF/PMA13/RPI42/RB10_23") (pintype "passive"))
    )
    (net (code "45") (name "/SPI_TXD") (class "Default")
      (node (ref "U3") (pin "5") (pinfunction "C1IN1-/SDI2/PMA4/RPI119/RG7_5") (pintype "passive"))
    )
    (net (code "46") (name "/USB5.0V") (class "Default")
      (node (ref "D6") (pin "4") (pinfunction "4_4") (pintype "passive"))
      (node (ref "D6") (pin "6") (pinfunction "6_6") (pintype "passive"))
      (node (ref "J2") (pin "1") (pinfunction "1_1") (pintype "passive"))
      (node (ref "R10") (pin "1") (pinfunction "1_1") (pintype "passive"))
      (node (ref "R11") (pin "2") (pinfunction "2_2") (pintype "passive"))
    )
    (net (code "47") (name "/VCAP") (class "Default")
      (node (ref "C2") (pin "1") (pinfunction "1_1") (pintype "passive"))
      (node (ref "U3") (pin "56") (pinfunction "VCAP_56") (pintype "passive"))
    )
    (net (code "48") (name "/VDD_PLL") (class "Default")
      (node (ref "C18") (pin "1") (pinfunction "1_1") (pintype "passive"))
      (node (ref "FB1") (pin "2") (pinfunction "2_2") (pintype "passive"))
    )
    (net (code "49") (name "/XCLK1") (class "Default")
      (node (ref "R7") (pin "2") (pinfunction "2_2") (pintype "passive"))
      (node (ref "U3") (pin "46") (pinfunction "INT0/DMH/RP64/RD0_46") (pintype "passive"))
      (node (ref "U3") (pin "49") (pinfunction "VCPCON/RP65/RD1_49") (pintype "passive"))
      (node (ref "U3") (pin "52") (pinfunction "PMWR/RP68/RD4_52") (pintype "passive"))
      (node (ref "U3") (pin "53") (pinfunction "PMRD/RP69/RD5_53") (pintype "passive"))
    )
    (net (code "50") (name "/YELLOW") (class "Default")
      (node (ref "D3") (pin "2") (pinfunction "A_2") (pintype "passive"))
      (node (ref "U3") (pin "44") (pinfunction "ASCL1/PMCS2/RPI74/RD10_44") (pintype "passive"))
    )
    (net (code "51") (name "GND") (class "Default")
      (node (ref "C1") (pin "2") (pinfunction "2_2") (pintype "passive"))
      (node (ref "C10") (pin "2") (pinfunction "2_2") (pintype "passive"))
      (node (ref "C11") (pin "2") (pinfunction "2_2") (pintype "passive"))
      (node (ref "C12") (pin "2") (pinfunction "2_2") (pintype "passive"))
      (node (ref "C13") (pin "1") (pinfunction "1_1") (pintype "passive"))
      (node (ref "C14") (pin "2") (pinfunction "2_2") (pintype "passive"))
      (node (ref "C15") (pin "2") (pinfunction "2_2") (pintype "passive"))
      (node (ref "C16") (pin "2") (pinfunction "2_2") (pintype "passive"))
      (node (ref "C17") (pin "2") (pinfunction "2_2") (pintype "passive"))
      (node (ref "C18") (pin "2") (pinfunction "2_2") (pintype "passive"))
      (node (ref "C19") (pin "2") (pinfunction "2_2") (pintype "passive"))
      (node (ref "C2") (pin "2") (pinfunction "2_2") (pintype "passive"))
      (node (ref "C3") (pin "2") (pinfunction "2_2") (pintype "passive"))
      (node (ref "C4") (pin "2") (pinfunction "2_2") (pintype "passive"))
      (node (ref "C5") (pin "2") (pinfunction "2_2") (pintype "passive"))
      (node (ref "C6") (pin "2") (pinfunction "2_2") (pintype "passive"))
      (node (ref "C7") (pin "2") (pinfunction "2_2") (pintype "passive"))
      (node (ref "C8") (pin "2") (pinfunction "2_2") (pintype "passive"))
      (node (ref "C9") (pin "2") (pinfunction "2_2") (pintype "passive"))
      (node (ref "D1") (pin "1") (pinfunction "C_1") (pintype "passive"))
      (node (ref "D2") (pin "1") (pinfunction "C_1") (pintype "passive"))
      (node (ref "D3") (pin "1") (pinfunction "C_1") (pintype "passive"))
      (node (ref "D4") (pin "1") (pinfunction "C_1") (pintype "passive"))
      (node (ref "D6") (pin "2") (pinfunction "2_2") (pintype "passive"))
      (node (ref "D6") (pin "5") (pinfunction "5_5") (pintype "passive"))
      (node (ref "D9") (pin "2") (pinfunction "A_2") (pintype "passive"))
      (node (ref "J1") (pin "3") (pinfunction "3_3") (pintype "passive"))
      (node (ref "J2") (pin "5") (pinfunction "5_5") (pintype "passive"))
      (node (ref "J2") (pin "6") (pinfunction "6_6") (pintype "passive"))
      (node (ref "J2") (pin "7") (pinfunction "7_7") (pintype "passive"))
      (node (ref "J2") (pin "8") (pinfunction "8_8") (pintype "passive"))
      (node (ref "J2") (pin "9") (pinfunction "9_9") (pintype "passive"))
      (node (ref "J3") (pin "2") (pinfunction "2_2") (pintype "passive"))
      (node (ref "J4") (pin "4") (pinfunction "4_4") (pintype "passive"))
      (node (ref "J4") (pin "5") (pinfunction "5_5") (pintype "passive"))
      (node (ref "J4") (pin "6") (pinfunction "6_6") (pintype "passive"))
      (node (ref "R17") (pin "2") (pinfunction "2_2") (pintype "passive"))
      (node (ref "R19") (pin "2") (pinfunction "2_2") (pintype "passive"))
      (node (ref "R26") (pin "2") (pinfunction "2_2") (pintype "passive"))
      (node (ref "R5") (pin "1") (pinfunction "1_1") (pintype "passive"))
      (node (ref "R8") (pin "2") (pinfunction "2_2") (pintype "passive"))
      (node (ref "U10") (pin "6") (pinfunction "GND_6") (pintype "passive"))
      (node (ref "U10") (pin "7") (pinfunction "GND_7") (pintype "passive"))
      (node (ref "U3") (pin "20") (pinfunction "AVSS_20") (pintype "passive"))
      (node (ref "U3") (pin "25") (pinfunction "VSS_25") (pintype "passive"))
      (node (ref "U3") (pin "41") (pinfunction "VSS_41") (pintype "passive"))
      (node (ref "U3") (pin "9") (pinfunction "VSS_9") (pintype "passive"))
      (node (ref "U4") (pin "2") (pinfunction "GND_2") (pintype "passive"))
      (node (ref "U4") (pin "3") (pinfunction "GND_3") (pintype "passive"))
      (node (ref "U4") (pin "4") (pinfunction "N.C._4") (pintype "passive"))
      (node (ref "U4") (pin "5") (pinfunction "N.C._5") (pintype "passive"))
      (node (ref "U4") (pin "6") (pinfunction "GND_6") (pintype "passive"))
      (node (ref "U4") (pin "7") (pinfunction "GND_7") (pintype "passive"))
      (node (ref "U5") (pin "2") (pinfunction "GND_2") (pintype "passive"))
      (node (ref "U6") (pin "6") (pinfunction "GND_6") (pintype "passive"))
      (node (ref "U6") (pin "7") (pinfunction "GND_7") (pintype "passive"))
      (node (ref "U7") (pin "4") (pinfunction "GND_4") (pintype "passive"))
      (node (ref "U8") (pin "4") (pinfunction "GND_4") (pintype "passive"))
      (node (ref "U9") (pin "6") (pinfunction "GND_6") (pintype "passive"))
      (node (ref "U9") (pin "7") (pinfunction "GND_7") (pintype "passive"))
    )
    (net (code "52") (name "Net-(U3-AN2{slash}C2IN2-{slash}VMIO{slash}RPI34{slash}RB2)") (class "Default")
      (node (ref "TP7") (pin "1") (pinfunction "1_1") (pintype "passive"))
      (node (ref "U3") (pin "14") (pinfunction "AN2/C2IN2-/VMIO/RPI34/RB2_14") (pintype "passive"))
    )
    (net (code "53") (name "Net-(U3-AN3{slash}C2IN1+{slash}VPIO{slash}RPI35{slash}RB3)") (class "Default")
      (node (ref "TP6") (pin "1") (pinfunction "1_1") (pintype "passive"))
      (node (ref "U3") (pin "13") (pinfunction "AN3/C2IN1+/VPIO/RPI35/RB3_13") (pintype "passive"))
    )
    (net (code "54") (name "Net-(U3-AN4{slash}C1IN2-{slash}USBOEN{slash}RPI36{slash}RB4)") (class "Default")
      (node (ref "TP5") (pin "1") (pinfunction "1_1") (pintype "passive"))
      (node (ref "U3") (pin "12") (pinfunction "AN4/C1IN2-/USBOEN/RPI36/RB4_12") (pintype "passive"))
    )
    (net (code "55") (name "Net-(U3-AN5{slash}C1IN1+{slash}VBUSON{slash}VBUSST{slash}RPI37{slash}RB5)") (class "Default")
      (node (ref "TP3") (pin "1") (pinfunction "1_1") (pintype "passive"))
      (node (ref "U3") (pin "11") (pinfunction "AN5/C1IN1+/VBUSON/VBUSST/RPI37/RB5_11") (pintype "passive"))
    )
    (net (code "56") (name "Net-(U3-AN8{slash}PMA6{slash}RPI40{slash}RB8)") (class "Default")
      (node (ref "TP10") (pin "1") (pinfunction "1_1") (pintype "passive"))
      (node (ref "U3") (pin "21") (pinfunction "AN8/PMA6/RPI40/RB8_21") (pintype "passive"))
    )
    (net (code "57") (name "Net-(U3-AN9{slash}PMA7{slash}{slash}RPI41{slash}RB9)") (class "Default")
      (node (ref "TP11") (pin "1") (pinfunction "1_1") (pintype "passive"))
      (node (ref "U3") (pin "22") (pinfunction "AN9/PMA7//RPI41/RB9_22") (pintype "passive"))
    )
    (net (code "58") (name "Net-(U3-ASDA1{slash}DPLN{slash}RPI73{slash}RD9)") (class "Default")
      (node (ref "TP12") (pin "1") (pinfunction "1_1") (pintype "passive"))
      (node (ref "U3") (pin "43") (pinfunction "ASDA1/DPLN/RPI73/RD9_43") (pintype "passive"))
    )
    (net (code "59") (name "Net-(U3-C3IN2-{slash}RP70{slash}RD6)") (class "Default")
      (node (ref "TP4") (pin "1") (pinfunction "1_1") (pintype "passive"))
      (node (ref "U3") (pin "54") (pinfunction "C3IN2-/RP70/RD6_54") (pintype "passive"))
    )
    (net (code "60") (name "Net-(U3-DPH{slash}RP66{slash}RD2)") (class "Default")
      (node (ref "TP9") (pin "1") (pinfunction "1_1") (pintype "passive"))
      (node (ref "U3") (pin "50") (pinfunction "DPH/RP66/RD2_50") (pintype "passive"))
    )
    (net (code "61") (name "Net-(U3-PMBE{slash}RP67{slash}RD3)") (class "Default")
      (node (ref "TP8") (pin "1") (pinfunction "1_1") (pintype "passive"))
      (node (ref "U3") (pin "51") (pinfunction "PMBE/RP67/RD3_51") (pintype "passive"))
    )
    (net (code "62") (name "Net-(U3-RTCC{slash}DMLN{slash}RPI72{slash}RD8)") (class "Default")
      (node (ref "TP13") (pin "1") (pinfunction "1_1") (pintype "passive"))
      (node (ref "U3") (pin "42") (pinfunction "RTCC/DMLN/RPI72/RD8_42") (pintype "passive"))
    )
    (net (code "63") (name "Net-(U3-USBID{slash}RP99{slash}RF3)") (class "Default")
      (node (ref "TP21") (pin "1") (pinfunction "1_1") (pintype "passive"))
      (node (ref "U3") (pin "33") (pinfunction "USBID/RP99/RF3_33") (pintype "passive"))
    )
    (net (code "64") (name "Net-(U9-ADJ)") (class "Default")
      (node (ref "R16") (pin "2") (pinfunction "2_2") (pintype "passive"))
      (node (ref "R17") (pin "1") (pinfunction "1_1") (pintype "passive"))
      (node (ref "U9") (pin "2") (pinfunction "ADJ_2") (pintype "passive"))
    )
    (net (code "65") (name "Net-(U10-ADJ)") (class "Default")
      (node (ref "R18") (pin "2") (pinfunction "2_2") (pintype "passive"))
      (node (ref "R19") (pin "1") (pinfunction "1_1") (pintype "passive"))
      (node (ref "U10") (pin "2") (pinfunction "ADJ_2") (pintype "passive"))
    )
    (net (code "66") (name "unconnected-(J2-Pad4)") (class "Default")
      (node (ref "J2") (pin "4") (pinfunction "4_4") (pintype "passive"))
    )
    (net (code "67") (name "unconnected-(U5-N.C.-Pad4)") (class "Default")
      (node (ref "U5") (pin "4") (pinfunction "N.C._4") (pintype "passive+no_connect"))
    )
    (net (code "68") (name "unconnected-(U6-NC-Pad2)") (class "Default")
      (node (ref "U6") (pin "2") (pinfunction "NC_2") (pintype "passive+no_connect"))
    )
    (net (code "69") (name "unconnected-(U6-NC-Pad3)") (class "Default")
      (node (ref "U6") (pin "3") (pinfunction "NC_3") (pintype "passive+no_connect"))
    )
    (net (code "70") (name "unconnected-(U6-NC-Pad4)") (class "Default")
      (node (ref "U6") (pin "4") (pinfunction "NC_4") (pintype "passive+no_connect"))
    )
    (net (code "71") (name "unconnected-(U9-NC-Pad3)") (class "Default")
      (node (ref "U9") (pin "3") (pinfunction "NC_3") (pintype "passive+no_connect"))
    )
    (net (code "72") (name "unconnected-(U9-NC-Pad4)") (class "Default")
      (node (ref "U9") (pin "4") (pinfunction "NC_4") (pintype "passive+no_connect"))
    )
    (net (code "73") (name "unconnected-(U10-NC-Pad3)") (class "Default")
      (node (ref "U10") (pin "3") (pinfunction "NC_3") (pintype "passive+no_connect"))
    )
    (net (code "74") (name "unconnected-(U10-NC-Pad4)") (class "Default")
      (node (ref "U10") (pin "4") (pinfunction "NC_4") (pintype "passive+no_connect"))
    )
  )
)
